# BNC-V003.net
KiCad netlist of a schematic drawn in EAGLE
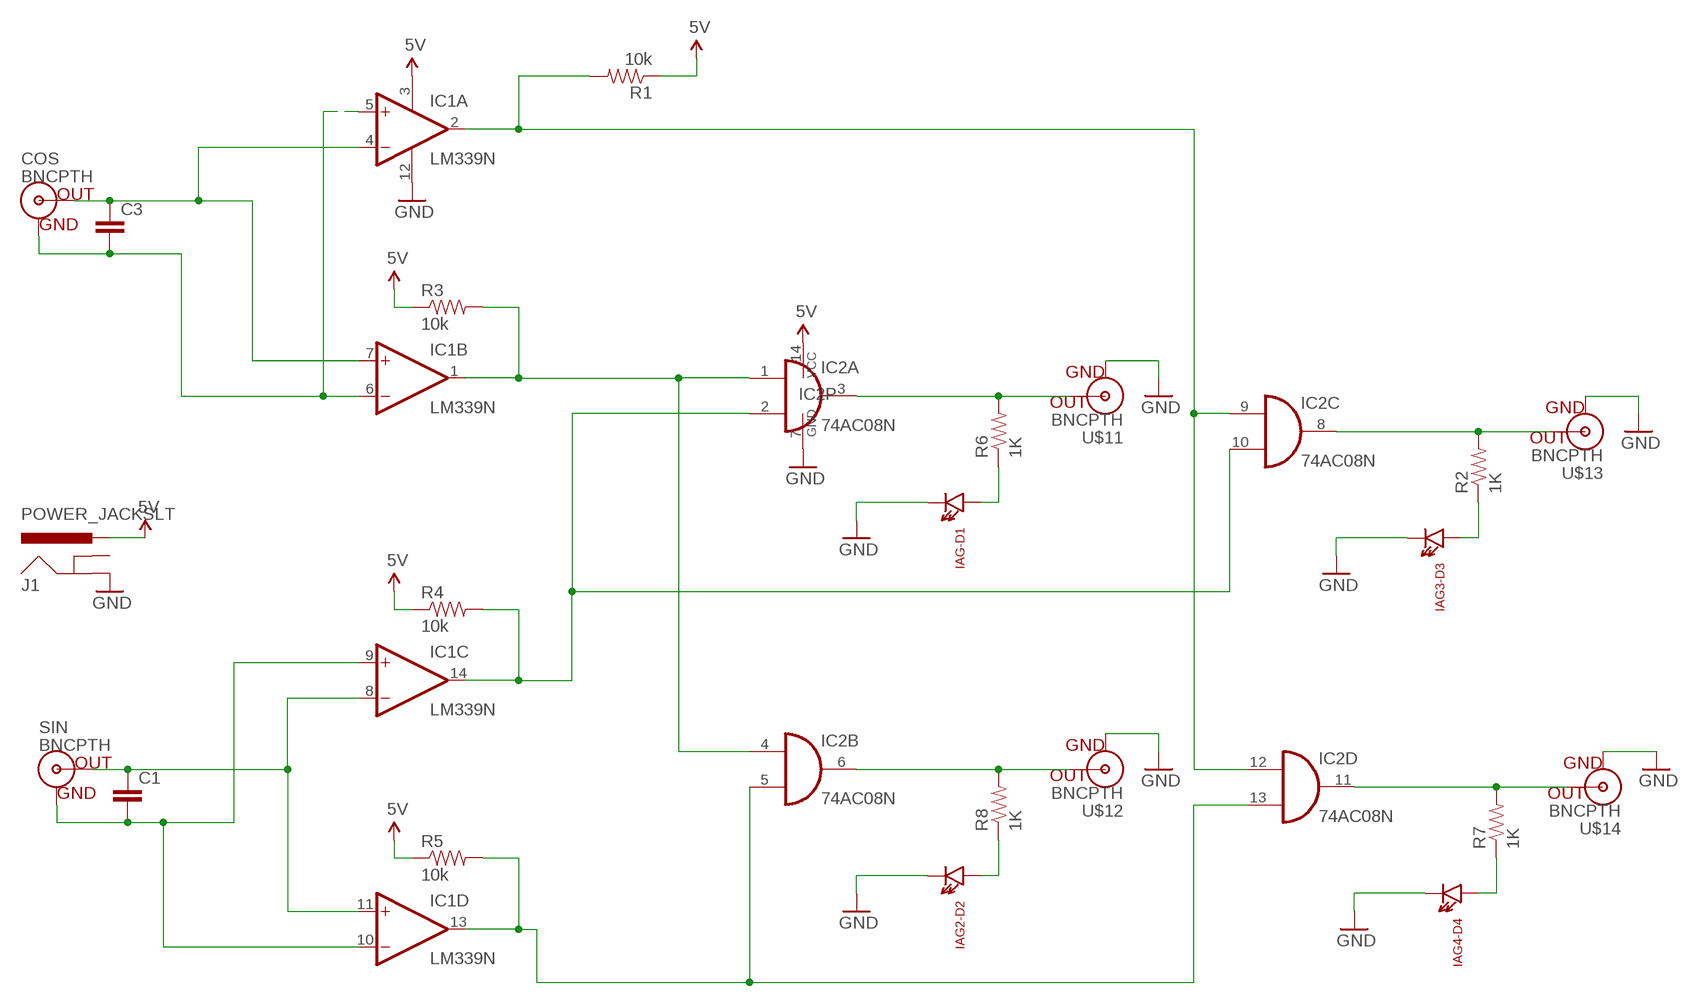
[diagram p0: schematic, sheet 1]

(export (version "E")
  (design (tool "Eeschema 10.0.6"))
  (components
    (comp (ref "C1")
      (value "0.1UF-50V-20%(PTH)KIT-EZ")
      (footprint "eagle-import:CAP-PTH-SMALL-KIT")
      (libsource (lib "eagle-import") (part "0.1UF-50V-20%(PTH)KIT-EZ"))
    )
    (comp (ref "C3")
      (value "0.1UF-50V-20%(PTH)KIT-EZ")
      (footprint "eagle-import:CAP-PTH-SMALL-KIT")
      (libsource (lib "eagle-import") (part "0.1UF-50V-20%(PTH)KIT-EZ"))
    )
    (comp (ref "COS")
      (value "BNCPTH")
      (footprint "eagle-import:BNC")
      (libsource (lib "eagle-import") (part "BNCPTH"))
    )
    (comp (ref "IAG-D1")
      (value "LTE-302")
      (footprint "eagle-import:LTE-302")
      (libsource (lib "eagle-import") (part "LTE-302"))
    )
    (comp (ref "IAG2-D2")
      (value "LTE-302")
      (footprint "eagle-import:LTE-302")
      (libsource (lib "eagle-import") (part "LTE-302"))
    )
    (comp (ref "IAG3-D3")
      (value "LTE-302")
      (footprint "eagle-import:LTE-302")
      (libsource (lib "eagle-import") (part "LTE-302"))
    )
    (comp (ref "IAG4-D4")
      (value "LTE-302")
      (footprint "eagle-import:LTE-302")
      (libsource (lib "eagle-import") (part "LTE-302"))
    )
    (comp (ref "IC1")
      (value "LM339N")
      (footprint "eagle-import:DIL14")
      (libsource (lib "eagle-import") (part "LM339N"))
    )
    (comp (ref "IC2")
      (value "74AC08N")
      (footprint "eagle-import:DIL14")
      (libsource (lib "eagle-import") (part "7408NAC"))
    )
    (comp (ref "J1")
      (value "POWER_JACKSLT")
      (footprint "eagle-import:POWER_JACK_SLOT")
      (libsource (lib "eagle-import") (part "POWER_JACKSLT"))
    )
    (comp (ref "R1")
      (value "10k")
      (footprint "eagle-import:AXIAL-0.3")
      (libsource (lib "eagle-import") (part "10KOHM-1/4W-1%(PTH)HORIZ"))
    )
    (comp (ref "R2")
      (value "1K")
      (footprint "eagle-import:AXIAL-0.3")
      (libsource (lib "eagle-import") (part "1KOHM-1/4W-1%(PTH)"))
    )
    (comp (ref "R3")
      (value "10k")
      (footprint "eagle-import:AXIAL-0.3")
      (libsource (lib "eagle-import") (part "10KOHM-1/4W-1%(PTH)HORIZ"))
    )
    (comp (ref "R4")
      (value "10k")
      (footprint "eagle-import:AXIAL-0.3")
      (libsource (lib "eagle-import") (part "10KOHM-1/4W-1%(PTH)HORIZ"))
    )
    (comp (ref "R5")
      (value "10k")
      (footprint "eagle-import:AXIAL-0.3")
      (libsource (lib "eagle-import") (part "10KOHM-1/4W-1%(PTH)HORIZ"))
    )
    (comp (ref "R6")
      (value "1K")
      (footprint "eagle-import:AXIAL-0.3")
      (libsource (lib "eagle-import") (part "1KOHM-1/4W-1%(PTH)"))
    )
    (comp (ref "R7")
      (value "1K")
      (footprint "eagle-import:AXIAL-0.3")
      (libsource (lib "eagle-import") (part "1KOHM-1/4W-1%(PTH)"))
    )
    (comp (ref "R8")
      (value "1K")
      (footprint "eagle-import:AXIAL-0.3")
      (libsource (lib "eagle-import") (part "1KOHM-1/4W-1%(PTH)"))
    )
    (comp (ref "SIN")
      (value "BNCPTH")
      (footprint "eagle-import:BNC")
      (libsource (lib "eagle-import") (part "BNCPTH"))
    )
    (comp (ref "U$11")
      (value "BNCPTH")
      (footprint "eagle-import:BNC")
      (libsource (lib "eagle-import") (part "BNCPTH"))
    )
    (comp (ref "U$12")
      (value "BNCPTH")
      (footprint "eagle-import:BNC")
      (libsource (lib "eagle-import") (part "BNCPTH"))
    )
    (comp (ref "U$13")
      (value "BNCPTH")
      (footprint "eagle-import:BNC")
      (libsource (lib "eagle-import") (part "BNCPTH"))
    )
    (comp (ref "U$14")
      (value "BNCPTH")
      (footprint "eagle-import:BNC")
      (libsource (lib "eagle-import") (part "BNCPTH"))
    )
  )
  (nets
    (net (code "1") (name "5V") (class "Default")
      (node (ref "IC1") (pin "3") (pinfunction "V+_3") (pintype "power_in"))
      (node (ref "IC2") (pin "14") (pinfunction "VCC_14") (pintype "power_in"))
      (node (ref "J1") (pin "PWR") (pinfunction "PWR_PWR") (pintype "bidirectional"))
      (node (ref "R1") (pin "P$1") (pinfunction "1_P$1") (pintype "passive"))
      (node (ref "R3") (pin "P$1") (pinfunction "1_P$1") (pintype "passive"))
      (node (ref "R4") (pin "P$1") (pinfunction "1_P$1") (pintype "passive"))
      (node (ref "R5") (pin "P$1") (pinfunction "1_P$1") (pintype "passive"))
    )
    (net (code "2") (name "GND") (class "Default")
      (node (ref "IAG-D1") (pin "C") (pinfunction "C_C") (pintype "bidirectional"))
      (node (ref "IAG2-D2") (pin "C") (pinfunction "C_C") (pintype "bidirectional"))
      (node (ref "IAG3-D3") (pin "C") (pinfunction "C_C") (pintype "bidirectional"))
      (node (ref "IAG4-D4") (pin "C") (pinfunction "C_C") (pintype "bidirectional"))
      (node (ref "IC1") (pin "12") (pinfunction "GND_12") (pintype "power_in"))
      (node (ref "IC2") (pin "7") (pinfunction "GND_7") (pintype "power_in"))
      (node (ref "J1") (pin "GND@2") (pinfunction "GND_GND@2") (pintype "bidirectional"))
      (node (ref "U$11") (pin "GND") (pinfunction "GND_GND") (pintype "bidirectional"))
      (node (ref "U$12") (pin "GND") (pinfunction "GND_GND") (pintype "bidirectional"))
      (node (ref "U$13") (pin "GND") (pinfunction "GND_GND") (pintype "bidirectional"))
      (node (ref "U$14") (pin "GND") (pinfunction "GND_GND") (pintype "bidirectional"))
    )
    (net (code "3") (name "Net-(COS-OUT)") (class "Default")
      (node (ref "C3") (pin "1") (pinfunction "1_1") (pintype "passive"))
      (node (ref "COS") (pin "S") (pinfunction "OUT_S") (pintype "bidirectional"))
      (node (ref "IC1") (pin "4") (pinfunction "-IN_4") (pintype "input"))
      (node (ref "IC1") (pin "7") (pinfunction "+IN_7") (pintype "input"))
    )
    (net (code "4") (name "Net-(IC1A-+IN)") (class "Default")
      (node (ref "C3") (pin "2") (pinfunction "2_2") (pintype "passive"))
      (node (ref "COS") (pin "GND") (pinfunction "GND_GND") (pintype "bidirectional"))
      (node (ref "IC1") (pin "5") (pinfunction "+IN_5") (pintype "input"))
      (node (ref "IC1") (pin "6") (pinfunction "-IN_6") (pintype "input"))
    )
    (net (code "5") (name "Net-(IC1A-OUT)") (class "Default")
      (node (ref "IC1") (pin "2") (pinfunction "OUT_2") (pintype "open_collector"))
      (node (ref "IC2") (pin "12") (pinfunction "I0_12") (pintype "input"))
      (node (ref "IC2") (pin "9") (pinfunction "I0_9") (pintype "input"))
      (node (ref "R1") (pin "P$2") (pinfunction "2_P$2") (pintype "passive"))
    )
    (net (code "6") (name "Net-(IC1B-OUT)") (class "Default")
      (node (ref "IC1") (pin "1") (pinfunction "OUT_1") (pintype "open_collector"))
      (node (ref "IC2") (pin "1") (pinfunction "I0_1") (pintype "input"))
      (node (ref "IC2") (pin "4") (pinfunction "I0_4") (pintype "input"))
      (node (ref "R3") (pin "P$2") (pinfunction "2_P$2") (pintype "passive"))
    )
    (net (code "7") (name "Net-(IC1C-+IN)") (class "Default")
      (node (ref "C1") (pin "2") (pinfunction "2_2") (pintype "passive"))
      (node (ref "IC1") (pin "10") (pinfunction "-IN_10") (pintype "input"))
      (node (ref "IC1") (pin "9") (pinfunction "+IN_9") (pintype "input"))
      (node (ref "SIN") (pin "GND") (pinfunction "GND_GND") (pintype "bidirectional"))
    )
    (net (code "8") (name "Net-(IC1C--IN)") (class "Default")
      (node (ref "C1") (pin "1") (pinfunction "1_1") (pintype "passive"))
      (node (ref "IC1") (pin "11") (pinfunction "+IN_11") (pintype "input"))
      (node (ref "IC1") (pin "8") (pinfunction "-IN_8") (pintype "input"))
      (node (ref "SIN") (pin "S") (pinfunction "OUT_S") (pintype "bidirectional"))
    )
    (net (code "9") (name "Net-(IC1C-OUT)") (class "Default")
      (node (ref "IC1") (pin "14") (pinfunction "OUT_14") (pintype "open_collector"))
      (node (ref "IC2") (pin "10") (pinfunction "I1_10") (pintype "input"))
      (node (ref "IC2") (pin "2") (pinfunction "I1_2") (pintype "input"))
      (node (ref "R4") (pin "P$2") (pinfunction "2_P$2") (pintype "passive"))
    )
    (net (code "10") (name "Net-(IC1D-OUT)") (class "Default")
      (node (ref "IC1") (pin "13") (pinfunction "OUT_13") (pintype "open_collector"))
      (node (ref "IC2") (pin "13") (pinfunction "I1_13") (pintype "input"))
      (node (ref "IC2") (pin "5") (pinfunction "I1_5") (pintype "input"))
      (node (ref "R5") (pin "P$2") (pinfunction "2_P$2") (pintype "passive"))
    )
    (net (code "11") (name "Net-(IC2A-O)") (class "Default")
      (node (ref "IC2") (pin "3") (pinfunction "O_3") (pintype "output"))
      (node (ref "R6") (pin "P$2") (pinfunction "2_P$2") (pintype "passive"))
      (node (ref "U$11") (pin "S") (pinfunction "OUT_S") (pintype "bidirectional"))
    )
    (net (code "12") (name "Net-(IC2B-O)") (class "Default")
      (node (ref "IC2") (pin "6") (pinfunction "O_6") (pintype "output"))
      (node (ref "R8") (pin "P$2") (pinfunction "2_P$2") (pintype "passive"))
      (node (ref "U$12") (pin "S") (pinfunction "OUT_S") (pintype "bidirectional"))
    )
    (net (code "13") (name "Net-(IC2C-O)") (class "Default")
      (node (ref "IC2") (pin "8") (pinfunction "O_8") (pintype "output"))
      (node (ref "R2") (pin "P$2") (pinfunction "2_P$2") (pintype "passive"))
      (node (ref "U$13") (pin "S") (pinfunction "OUT_S") (pintype "bidirectional"))
    )
    (net (code "14") (name "Net-(IC2D-O)") (class "Default")
      (node (ref "IC2") (pin "11") (pinfunction "O_11") (pintype "output"))
      (node (ref "R7") (pin "P$2") (pinfunction "2_P$2") (pintype "passive"))
      (node (ref "U$14") (pin "S") (pinfunction "OUT_S") (pintype "bidirectional"))
    )
    (net (code "15") (name "Net-(R2-1)") (class "Default")
      (node (ref "IAG3-D3") (pin "A") (pinfunction "A_A") (pintype "bidirectional"))
      (node (ref "R2") (pin "P$1") (pinfunction "1_P$1") (pintype "passive"))
    )
    (net (code "16") (name "Net-(R6-1)") (class "Default")
      (node (ref "IAG-D1") (pin "A") (pinfunction "A_A") (pintype "bidirectional"))
      (node (ref "R6") (pin "P$1") (pinfunction "1_P$1") (pintype "passive"))
    )
    (net (code "17") (name "Net-(R7-1)") (class "Default")
      (node (ref "IAG4-D4") (pin "A") (pinfunction "A_A") (pintype "bidirectional"))
      (node (ref "R7") (pin "P$1") (pinfunction "1_P$1") (pintype "passive"))
    )
    (net (code "18") (name "Net-(R8-1)") (class "Default")
      (node (ref "IAG2-D2") (pin "A") (pinfunction "A_A") (pintype "bidirectional"))
      (node (ref "R8") (pin "P$1") (pinfunction "1_P$1") (pintype "passive"))
    )
    (net (code "19") (name "unconnected-(J1-GNDBREAK-PadGND@1)") (class "Default")
      (node (ref "J1") (pin "GND@1") (pinfunction "GNDBREAK_GND@1") (pintype "bidirectional"))
    )
  )
)
